# Final_board_R1_1.net
KiCad netlist of a schematic drawn in EAGLE
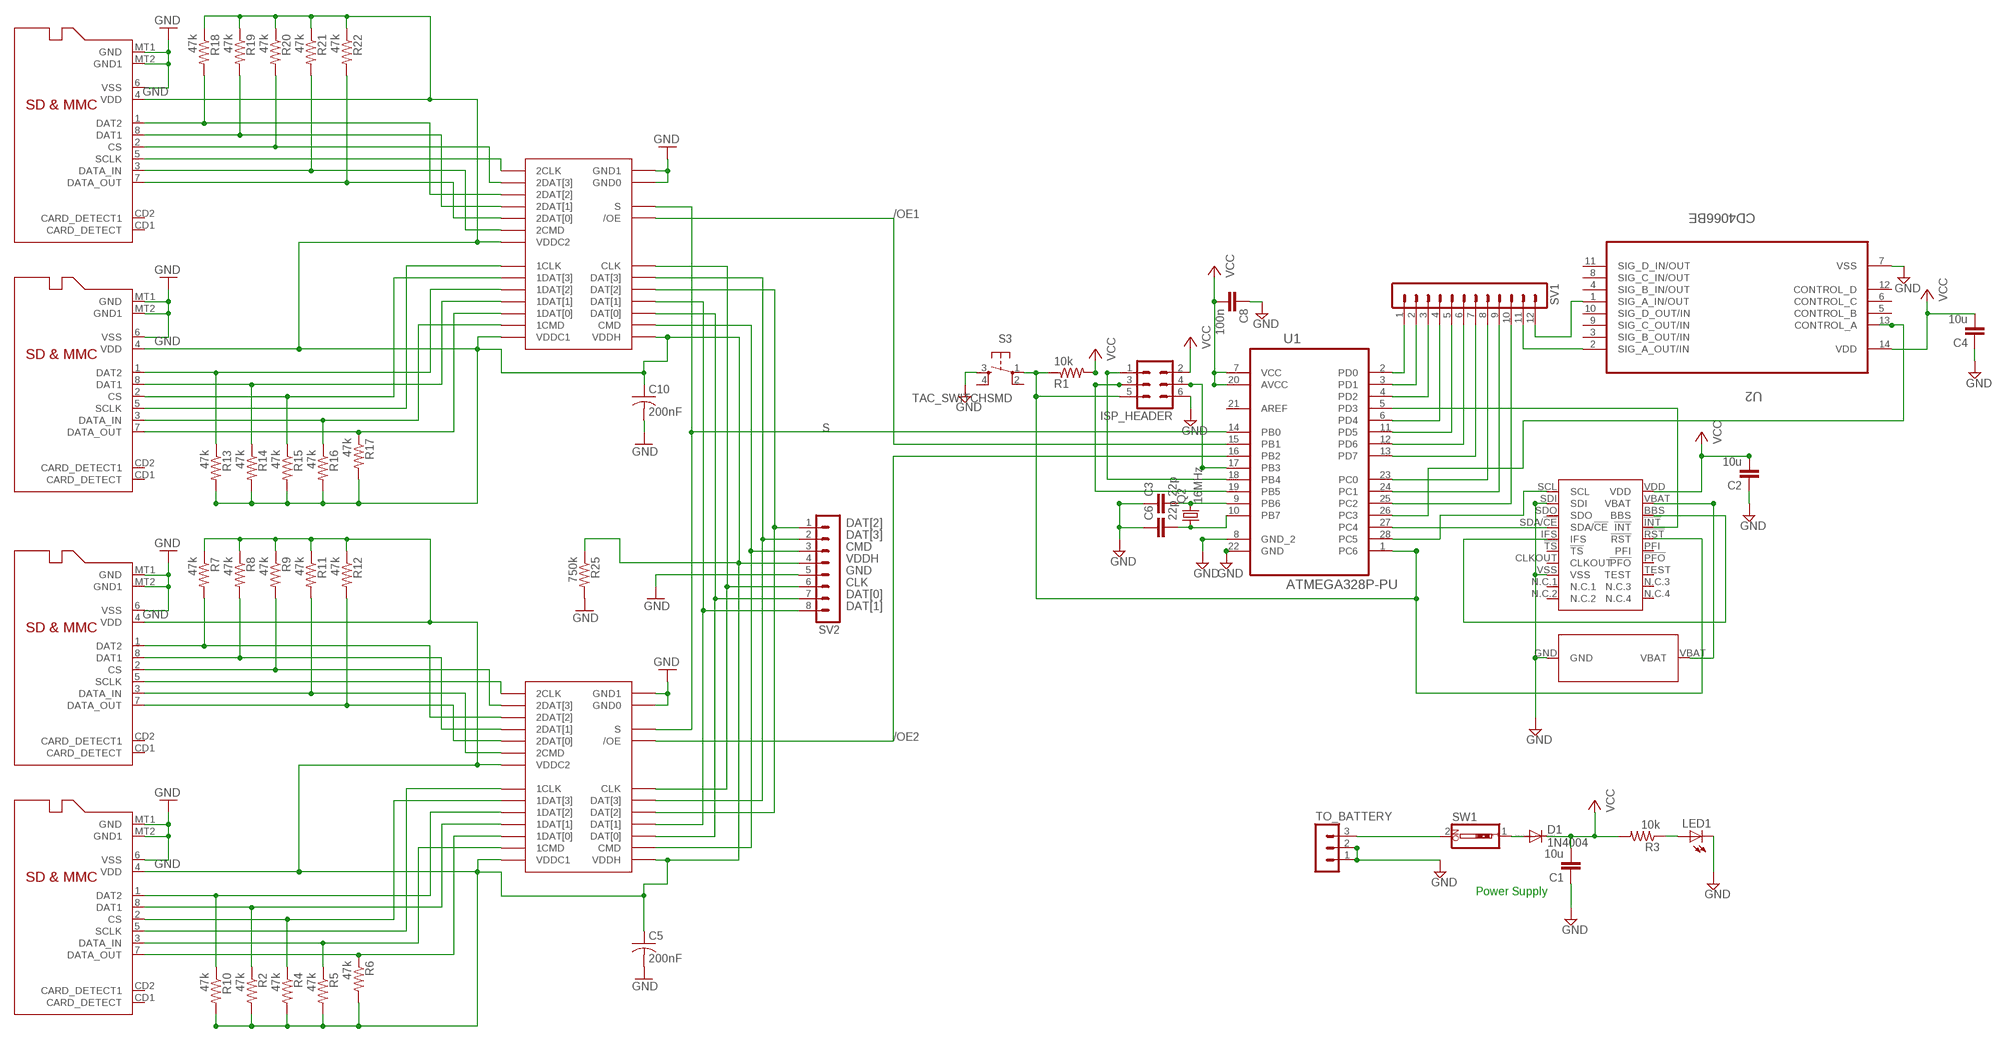
[diagram p0: schematic, sheet 1]

(export (version "E")
  (design (tool "Eeschema 10.0.6"))
  (components
    (comp (ref "+3.6V")
      (value "FSSD06")
      (footprint "eagle-import:MLP-24")
      (libsource (lib "eagle-import") (part "FSSD06"))
    )
    (comp (ref "+3.6V1")
      (value "FSSD06")
      (footprint "eagle-import:MLP-24")
      (libsource (lib "eagle-import") (part "FSSD06"))
    )
    (comp (ref "C1")
      (value "10u")
      (footprint "eagle-import:C0805")
      (libsource (lib "eagle-import") (part "C-EUC0805"))
    )
    (comp (ref "C2")
      (value "10u")
      (footprint "eagle-import:C0805")
      (libsource (lib "eagle-import") (part "C-EUC0805"))
    )
    (comp (ref "C3")
      (value "22p")
      (footprint "eagle-import:C0805")
      (libsource (lib "eagle-import") (part "C-EUC0805"))
    )
    (comp (ref "C4")
      (value "10u")
      (footprint "eagle-import:C0805")
      (libsource (lib "eagle-import") (part "C-EUC0805"))
    )
    (comp (ref "C5")
      (value "200nF")
      (footprint "eagle-import:C0805")
      (libsource (lib "eagle-import") (part "C-USC0805"))
    )
    (comp (ref "C6")
      (value "22p")
      (footprint "eagle-import:C0805")
      (libsource (lib "eagle-import") (part "C-EUC0805"))
    )
    (comp (ref "C8")
      (value "100n")
      (footprint "eagle-import:C0805")
      (libsource (lib "eagle-import") (part "C-EUC0805"))
    )
    (comp (ref "C10")
      (value "200nF")
      (footprint "eagle-import:C0805")
      (libsource (lib "eagle-import") (part "C-USC0805"))
    )
    (comp (ref "D1")
      (value "1N4004")
      (footprint "eagle-import:DO41-10")
      (libsource (lib "eagle-import") (part "1N4004"))
    )
    (comp (ref "ISP_HEADER")
      (value "MA03-2")
      (footprint "eagle-import:MA03-2")
      (libsource (lib "eagle-import") (part "MA03-2"))
    )
    (comp (ref "LED1")
      (value "LEDCHIPLED_0805")
      (footprint "eagle-import:CHIPLED_0805")
      (libsource (lib "eagle-import") (part "LEDCHIPLED_0805"))
    )
    (comp (ref "Q2")
      (value "16MHz")
      (footprint "eagle-import:HC49_S")
      (libsource (lib "eagle-import") (part "CRYSTALHC49S"))
    )
    (comp (ref "R1")
      (value "10k")
      (footprint "eagle-import:R0805")
      (libsource (lib "eagle-import") (part "R-US_R0805"))
    )
    (comp (ref "R2")
      (value "47k")
      (footprint "eagle-import:R0805")
      (libsource (lib "eagle-import") (part "R-US_R0805"))
    )
    (comp (ref "R3")
      (value "10k")
      (footprint "eagle-import:R0805")
      (libsource (lib "eagle-import") (part "R-US_R0805"))
    )
    (comp (ref "R4")
      (value "47k")
      (footprint "eagle-import:R0805")
      (libsource (lib "eagle-import") (part "R-US_R0805"))
    )
    (comp (ref "R5")
      (value "47k")
      (footprint "eagle-import:R0805")
      (libsource (lib "eagle-import") (part "R-US_R0805"))
    )
    (comp (ref "R6")
      (value "47k")
      (footprint "eagle-import:R0805")
      (libsource (lib "eagle-import") (part "R-US_R0805"))
    )
    (comp (ref "R7")
      (value "47k")
      (footprint "eagle-import:R0805")
      (libsource (lib "eagle-import") (part "R-US_R0805"))
    )
    (comp (ref "R8")
      (value "47k")
      (footprint "eagle-import:R0805")
      (libsource (lib "eagle-import") (part "R-US_R0805"))
    )
    (comp (ref "R9")
      (value "47k")
      (footprint "eagle-import:R0805")
      (libsource (lib "eagle-import") (part "R-US_R0805"))
    )
    (comp (ref "R10")
      (value "47k")
      (footprint "eagle-import:R0805")
      (libsource (lib "eagle-import") (part "R-US_R0805"))
    )
    (comp (ref "R11")
      (value "47k")
      (footprint "eagle-import:R0805")
      (libsource (lib "eagle-import") (part "R-US_R0805"))
    )
    (comp (ref "R12")
      (value "47k")
      (footprint "eagle-import:R0805")
      (libsource (lib "eagle-import") (part "R-US_R0805"))
    )
    (comp (ref "R13")
      (value "47k")
      (footprint "eagle-import:R0805")
      (libsource (lib "eagle-import") (part "R-US_R0805"))
    )
    (comp (ref "R14")
      (value "47k")
      (footprint "eagle-import:R0805")
      (libsource (lib "eagle-import") (part "R-US_R0805"))
    )
    (comp (ref "R15")
      (value "47k")
      (footprint "eagle-import:R0805")
      (libsource (lib "eagle-import") (part "R-US_R0805"))
    )
    (comp (ref "R16")
      (value "47k")
      (footprint "eagle-import:R0805")
      (libsource (lib "eagle-import") (part "R-US_R0805"))
    )
    (comp (ref "R17")
      (value "47k")
      (footprint "eagle-import:R0805")
      (libsource (lib "eagle-import") (part "R-US_R0805"))
    )
    (comp (ref "R18")
      (value "47k")
      (footprint "eagle-import:R0805")
      (libsource (lib "eagle-import") (part "R-US_R0805"))
    )
    (comp (ref "R19")
      (value "47k")
      (footprint "eagle-import:R0805")
      (libsource (lib "eagle-import") (part "R-US_R0805"))
    )
    (comp (ref "R20")
      (value "47k")
      (footprint "eagle-import:R0805")
      (libsource (lib "eagle-import") (part "R-US_R0805"))
    )
    (comp (ref "R21")
      (value "47k")
      (footprint "eagle-import:R0805")
      (libsource (lib "eagle-import") (part "R-US_R0805"))
    )
    (comp (ref "R22")
      (value "47k")
      (footprint "eagle-import:R0805")
      (libsource (lib "eagle-import") (part "R-US_R0805"))
    )
    (comp (ref "R25")
      (value "750k")
      (footprint "eagle-import:R0805")
      (libsource (lib "eagle-import") (part "R-US_R0805"))
    )
    (comp (ref "S3")
      (value "TAC_SWITCHSMD")
      (footprint "eagle-import:TACTILE-SWITCH-SMD")
      (libsource (lib "eagle-import") (part "TAC_SWITCHSMD"))
    )
    (comp (ref "SV1")
      (value "MA12-1W")
      (footprint "eagle-import:MA12-1W")
      (libsource (lib "eagle-import") (part "MA12-1W"))
    )
    (comp (ref "SV2")
      (value "MA08-1")
      (footprint "eagle-import:MA08-1")
      (libsource (lib "eagle-import") (part "MA08-1"))
    )
    (comp (ref "SW1")
      (value "SW_DIP-1")
      (footprint "eagle-import:EDG-01")
      (libsource (lib "eagle-import") (part "SW_DIP-1"))
    )
    (comp (ref "TO_BATTERY")
      (value "MA03-1")
      (footprint "eagle-import:MA03-1")
      (libsource (lib "eagle-import") (part "MA03-1"))
    )
    (comp (ref "U$1")
      (value "RTC")
      (footprint "eagle-import:N5")
      (libsource (lib "eagle-import") (part "RTC"))
    )
    (comp (ref "U$2")
      (value "CR2032")
      (footprint "eagle-import:S8421R")
      (libsource (lib "eagle-import") (part "CR2032"))
    )
    (comp (ref "U1")
      (value "ATMEGA328P-PU")
      (footprint "eagle-import:DIP254P762X457-28")
      (libsource (lib "eagle-import") (part "ATMEGA328P-PU"))
    )
    (comp (ref "U2")
      (value "CD4066BE")
      (footprint "eagle-import:DIP254P762X508-14")
      (libsource (lib "eagle-import") (part "CD4066BE"))
    )
    (comp (ref "USD1")
      (value "MICROSD")
      (footprint "eagle-import:MICROSD")
      (libsource (lib "eagle-import") (part "MICROSD"))
    )
    (comp (ref "USD2")
      (value "MICROSD")
      (footprint "eagle-import:MICROSD")
      (libsource (lib "eagle-import") (part "MICROSD"))
    )
    (comp (ref "USD3")
      (value "MICROSD")
      (footprint "eagle-import:MICROSD")
      (libsource (lib "eagle-import") (part "MICROSD"))
    )
    (comp (ref "USD4")
      (value "MICROSD")
      (footprint "eagle-import:MICROSD")
      (libsource (lib "eagle-import") (part "MICROSD"))
    )
  )
  (nets
    (net (code "1") (name "/CLK") (class "Default")
      (node (ref "+3.6V") (pin "CLK") (pinfunction "CLK_CLK") (pintype "bidirectional"))
      (node (ref "+3.6V1") (pin "CLK") (pinfunction "CLK_CLK") (pintype "bidirectional"))
      (node (ref "SV2") (pin "6") (pinfunction "6_6") (pintype "passive"))
    )
    (net (code "2") (name "/CMD") (class "Default")
      (node (ref "+3.6V") (pin "CMD") (pinfunction "CMD_CMD") (pintype "bidirectional"))
      (node (ref "+3.6V1") (pin "CMD") (pinfunction "CMD_CMD") (pintype "bidirectional"))
      (node (ref "SV2") (pin "3") (pinfunction "3_3") (pintype "passive"))
    )
    (net (code "3") (name "/DAT[0]") (class "Default")
      (node (ref "+3.6V") (pin "DAT[0]") (pinfunction "DAT[0]_DAT[0]") (pintype "bidirectional"))
      (node (ref "+3.6V1") (pin "DAT[0]") (pinfunction "DAT[0]_DAT[0]") (pintype "bidirectional"))
      (node (ref "SV2") (pin "7") (pinfunction "7_7") (pintype "passive"))
    )
    (net (code "4") (name "/DAT[1]") (class "Default")
      (node (ref "+3.6V") (pin "DAT[1]") (pinfunction "DAT[1]_DAT[1]") (pintype "bidirectional"))
      (node (ref "+3.6V1") (pin "DAT[1]") (pinfunction "DAT[1]_DAT[1]") (pintype "bidirectional"))
      (node (ref "SV2") (pin "8") (pinfunction "8_8") (pintype "passive"))
    )
    (net (code "5") (name "/DAT[2]") (class "Default")
      (node (ref "+3.6V") (pin "DAT[2]") (pinfunction "DAT[2]_DAT[2]") (pintype "bidirectional"))
      (node (ref "+3.6V1") (pin "DAT[2]") (pinfunction "DAT[2]_DAT[2]") (pintype "bidirectional"))
      (node (ref "SV2") (pin "1") (pinfunction "1_1") (pintype "passive"))
    )
    (net (code "6") (name "/DAT[3]") (class "Default")
      (node (ref "+3.6V") (pin "DAT[3]") (pinfunction "DAT[3]_DAT[3]") (pintype "bidirectional"))
      (node (ref "+3.6V1") (pin "DAT[3]") (pinfunction "DAT[3]_DAT[3]") (pintype "bidirectional"))
      (node (ref "SV2") (pin "2") (pinfunction "2_2") (pintype "passive"))
    )
    (net (code "7") (name "/S") (class "Default")
      (node (ref "+3.6V") (pin "S") (pinfunction "S_S") (pintype "bidirectional"))
      (node (ref "+3.6V1") (pin "S") (pinfunction "S_S") (pintype "bidirectional"))
      (node (ref "U1") (pin "14") (pinfunction "PB0_14") (pintype "bidirectional"))
    )
    (net (code "8") (name "/VDDH") (class "Default")
      (node (ref "+3.6V") (pin "VDDC1") (pinfunction "VDDC1_VDDC1") (pintype "bidirectional"))
      (node (ref "+3.6V") (pin "VDDC2") (pinfunction "VDDC2_VDDC2") (pintype "bidirectional"))
      (node (ref "+3.6V") (pin "VDDH") (pinfunction "VDDH_VDDH") (pintype "bidirectional"))
      (node (ref "+3.6V1") (pin "VDDC1") (pinfunction "VDDC1_VDDC1") (pintype "bidirectional"))
      (node (ref "+3.6V1") (pin "VDDC2") (pinfunction "VDDC2_VDDC2") (pintype "bidirectional"))
      (node (ref "+3.6V1") (pin "VDDH") (pinfunction "VDDH_VDDH") (pintype "bidirectional"))
      (node (ref "C10") (pin "1") (pinfunction "1_1") (pintype "passive"))
      (node (ref "C5") (pin "1") (pinfunction "1_1") (pintype "passive"))
      (node (ref "R10") (pin "2") (pinfunction "2_2") (pintype "passive"))
      (node (ref "R11") (pin "1") (pinfunction "1_1") (pintype "passive"))
      (node (ref "R12") (pin "1") (pinfunction "1_1") (pintype "passive"))
      (node (ref "R13") (pin "2") (pinfunction "2_2") (pintype "passive"))
      (node (ref "R14") (pin "2") (pinfunction "2_2") (pintype "passive"))
      (node (ref "R15") (pin "2") (pinfunction "2_2") (pintype "passive"))
      (node (ref "R16") (pin "2") (pinfunction "2_2") (pintype "passive"))
      (node (ref "R17") (pin "2") (pinfunction "2_2") (pintype "passive"))
      (node (ref "R18") (pin "1") (pinfunction "1_1") (pintype "passive"))
      (node (ref "R19") (pin "1") (pinfunction "1_1") (pintype "passive"))
      (node (ref "R2") (pin "2") (pinfunction "2_2") (pintype "passive"))
      (node (ref "R20") (pin "1") (pinfunction "1_1") (pintype "passive"))
      (node (ref "R21") (pin "1") (pinfunction "1_1") (pintype "passive"))
      (node (ref "R22") (pin "1") (pinfunction "1_1") (pintype "passive"))
      (node (ref "R25") (pin "1") (pinfunction "1_1") (pintype "passive"))
      (node (ref "R4") (pin "2") (pinfunction "2_2") (pintype "passive"))
      (node (ref "R5") (pin "2") (pinfunction "2_2") (pintype "passive"))
      (node (ref "R6") (pin "2") (pinfunction "2_2") (pintype "passive"))
      (node (ref "R7") (pin "1") (pinfunction "1_1") (pintype "passive"))
      (node (ref "R8") (pin "1") (pinfunction "1_1") (pintype "passive"))
      (node (ref "R9") (pin "1") (pinfunction "1_1") (pintype "passive"))
      (node (ref "SV2") (pin "4") (pinfunction "4_4") (pintype "passive"))
      (node (ref "USD1") (pin "4") (pinfunction "VDD_4") (pintype "power_in"))
      (node (ref "USD2") (pin "4") (pinfunction "VDD_4") (pintype "power_in"))
      (node (ref "USD3") (pin "4") (pinfunction "VDD_4") (pintype "power_in"))
      (node (ref "USD4") (pin "4") (pinfunction "VDD_4") (pintype "power_in"))
    )
    (net (code "9") (name "/{slash}OE1") (class "Default")
      (node (ref "+3.6V1") (pin "/OE") (pinfunction "/OE_/OE") (pintype "bidirectional"))
      (node (ref "U1") (pin "15") (pinfunction "PB1_15") (pintype "bidirectional"))
    )
    (net (code "10") (name "/{slash}OE2") (class "Default")
      (node (ref "+3.6V") (pin "/OE") (pinfunction "/OE_/OE") (pintype "bidirectional"))
      (node (ref "U1") (pin "16") (pinfunction "PB2_16") (pintype "bidirectional"))
    )
    (net (code "11") (name "GND") (class "Default")
      (node (ref "+3.6V") (pin "GND0") (pinfunction "GND0_GND0") (pintype "bidirectional"))
      (node (ref "+3.6V") (pin "GND1") (pinfunction "GND1_GND1") (pintype "bidirectional"))
      (node (ref "+3.6V1") (pin "GND0") (pinfunction "GND0_GND0") (pintype "bidirectional"))
      (node (ref "+3.6V1") (pin "GND1") (pinfunction "GND1_GND1") (pintype "bidirectional"))
      (node (ref "C1") (pin "1") (pinfunction "1_1") (pintype "passive"))
      (node (ref "C10") (pin "2") (pinfunction "2_2") (pintype "passive"))
      (node (ref "C2") (pin "1") (pinfunction "1_1") (pintype "passive"))
      (node (ref "C3") (pin "1") (pinfunction "1_1") (pintype "passive"))
      (node (ref "C4") (pin "1") (pinfunction "1_1") (pintype "passive"))
      (node (ref "C5") (pin "2") (pinfunction "2_2") (pintype "passive"))
      (node (ref "C6") (pin "1") (pinfunction "1_1") (pintype "passive"))
      (node (ref "C8") (pin "1") (pinfunction "1_1") (pintype "passive"))
      (node (ref "ISP_HEADER") (pin "6") (pinfunction "6_6") (pintype "passive"))
      (node (ref "LED1") (pin "C") (pinfunction "C_C") (pintype "passive"))
      (node (ref "R25") (pin "2") (pinfunction "2_2") (pintype "passive"))
      (node (ref "S3") (pin "3") (pinfunction "3_3") (pintype "passive"))
      (node (ref "SV2") (pin "5") (pinfunction "5_5") (pintype "passive"))
      (node (ref "TO_BATTERY") (pin "1") (pinfunction "1_1") (pintype "passive"))
      (node (ref "TO_BATTERY") (pin "2") (pinfunction "2_2") (pintype "passive"))
      (node (ref "U$1") (pin "SDI") (pinfunction "SDI_SDI") (pintype "bidirectional"))
      (node (ref "U$1") (pin "VSS") (pinfunction "VSS_VSS") (pintype "bidirectional"))
      (node (ref "U$2") (pin "GND") (pinfunction "GND_GND") (pintype "bidirectional"))
      (node (ref "U1") (pin "22") (pinfunction "GND_22") (pintype "passive"))
      (node (ref "U1") (pin "8") (pinfunction "GND_2_8") (pintype "passive"))
      (node (ref "U2") (pin "7") (pinfunction "VSS_7") (pintype "passive"))
      (node (ref "USD1") (pin "6") (pinfunction "VSS_6") (pintype "power_in"))
      (node (ref "USD1") (pin "MT1") (pinfunction "GND_MT1") (pintype "power_in"))
      (node (ref "USD1") (pin "MT2") (pinfunction "GND1_MT2") (pintype "power_in"))
      (node (ref "USD2") (pin "6") (pinfunction "VSS_6") (pintype "power_in"))
      (node (ref "USD2") (pin "MT1") (pinfunction "GND_MT1") (pintype "power_in"))
      (node (ref "USD2") (pin "MT2") (pinfunction "GND1_MT2") (pintype "power_in"))
      (node (ref "USD3") (pin "6") (pinfunction "VSS_6") (pintype "power_in"))
      (node (ref "USD3") (pin "MT1") (pinfunction "GND_MT1") (pintype "power_in"))
      (node (ref "USD3") (pin "MT2") (pinfunction "GND1_MT2") (pintype "power_in"))
      (node (ref "USD4") (pin "6") (pinfunction "VSS_6") (pintype "power_in"))
      (node (ref "USD4") (pin "MT1") (pinfunction "GND_MT1") (pintype "power_in"))
      (node (ref "USD4") (pin "MT2") (pinfunction "GND1_MT2") (pintype "power_in"))
    )
    (net (code "12") (name "Net-(+3.6V-2CLK)") (class "Default")
      (node (ref "+3.6V") (pin "2CLCK") (pinfunction "2CLK_2CLCK") (pintype "bidirectional"))
      (node (ref "USD2") (pin "5") (pinfunction "SCLK_5") (pintype "input"))
    )
    (net (code "13") (name "Net-(+3.6V1-2CLK)") (class "Default")
      (node (ref "+3.6V1") (pin "2CLCK") (pinfunction "2CLK_2CLCK") (pintype "bidirectional"))
      (node (ref "USD4") (pin "5") (pinfunction "SCLK_5") (pintype "input"))
    )
    (net (code "14") (name "Net-(D1-PadA)") (class "Default")
      (node (ref "D1") (pin "A") (pinfunction "A_A") (pintype "passive"))
      (node (ref "SW1") (pin "1") (pinfunction "1_1") (pintype "passive"))
    )
    (net (code "15") (name "Net-(LED1-PadA)") (class "Default")
      (node (ref "LED1") (pin "A") (pinfunction "A_A") (pintype "passive"))
      (node (ref "R3") (pin "1") (pinfunction "1_1") (pintype "passive"))
    )
    (net (code "16") (name "Net-(SW1-Pad2)") (class "Default")
      (node (ref "SW1") (pin "2") (pinfunction "2_2") (pintype "passive"))
      (node (ref "TO_BATTERY") (pin "3") (pinfunction "3_3") (pintype "passive"))
    )
    (net (code "17") (name "Net-(U$1-PadBBS)") (class "Default")
      (node (ref "U$1") (pin "BBS") (pinfunction "BBS_BBS") (pintype "bidirectional"))
      (node (ref "U$1") (pin "IFS") (pinfunction "IFS_IFS") (pintype "bidirectional"))
    )
    (net (code "18") (name "Net-(U$1-PadVBAT)") (class "Default")
      (node (ref "U$1") (pin "VBAT") (pinfunction "VBAT_VBAT") (pintype "bidirectional"))
      (node (ref "U$2") (pin "VBAT") (pinfunction "VBAT_VBAT") (pintype "bidirectional"))
    )
    (net (code "19") (name "Net-(U$1-SDA{slash}~{CE})") (class "Default")
      (node (ref "U$1") (pin "SDA/!CE") (pinfunction "SDA/~{CE}_SDA/!CE") (pintype "bidirectional"))
      (node (ref "U1") (pin "27") (pinfunction "PC4_27") (pintype "bidirectional"))
    )
    (net (code "20") (name "Net-(U$1-~{INT})") (class "Default")
      (node (ref "U$1") (pin "!INT") (pinfunction "~{INT}_!INT") (pintype "bidirectional"))
      (node (ref "U1") (pin "5") (pinfunction "PD3_5") (pintype "bidirectional"))
    )
    (net (code "21") (name "Net-(U$1-~{RST})") (class "Default")
      (node (ref "ISP_HEADER") (pin "5") (pinfunction "5_5") (pintype "passive"))
      (node (ref "R1") (pin "1") (pinfunction "1_1") (pintype "passive"))
      (node (ref "S3") (pin "1") (pinfunction "1_1") (pintype "passive"))
      (node (ref "U$1") (pin "!RST") (pinfunction "~{RST}_!RST") (pintype "bidirectional"))
      (node (ref "U1") (pin "1") (pinfunction "PC6_1") (pintype "bidirectional"))
    )
    (net (code "22") (name "Net-(U1-PB3)") (class "Default")
      (node (ref "ISP_HEADER") (pin "4") (pinfunction "4_4") (pintype "passive"))
      (node (ref "U1") (pin "17") (pinfunction "PB3_17") (pintype "bidirectional"))
    )
    (net (code "23") (name "Net-(U1-PB4)") (class "Default")
      (node (ref "ISP_HEADER") (pin "1") (pinfunction "1_1") (pintype "passive"))
      (node (ref "U1") (pin "18") (pinfunction "PB4_18") (pintype "bidirectional"))
    )
    (net (code "24") (name "Net-(U1-PB5)") (class "Default")
      (node (ref "ISP_HEADER") (pin "3") (pinfunction "3_3") (pintype "passive"))
      (node (ref "U1") (pin "19") (pinfunction "PB5_19") (pintype "bidirectional"))
    )
    (net (code "25") (name "Net-(U1-PB6)") (class "Default")
      (node (ref "C3") (pin "2") (pinfunction "2_2") (pintype "passive"))
      (node (ref "Q2") (pin "2") (pinfunction "2_2") (pintype "passive"))
      (node (ref "U1") (pin "9") (pinfunction "PB6_9") (pintype "bidirectional"))
    )
    (net (code "26") (name "Net-(U1-PB7)") (class "Default")
      (node (ref "C6") (pin "2") (pinfunction "2_2") (pintype "passive"))
      (node (ref "Q2") (pin "1") (pinfunction "1_1") (pintype "passive"))
      (node (ref "U1") (pin "10") (pinfunction "PB7_10") (pintype "bidirectional"))
    )
    (net (code "27") (name "Net-(U1-PC0)") (class "Default")
      (node (ref "SV1") (pin "8") (pinfunction "8_8") (pintype "passive"))
      (node (ref "U1") (pin "23") (pinfunction "PC0_23") (pintype "bidirectional"))
    )
    (net (code "28") (name "Net-(U1-PC1)") (class "Default")
      (node (ref "SV1") (pin "9") (pinfunction "9_9") (pintype "passive"))
      (node (ref "U1") (pin "24") (pinfunction "PC1_24") (pintype "bidirectional"))
    )
    (net (code "29") (name "Net-(U1-PC2)") (class "Default")
      (node (ref "SV1") (pin "10") (pinfunction "10_10") (pintype "passive"))
      (node (ref "U1") (pin "25") (pinfunction "PC2_25") (pintype "bidirectional"))
    )
    (net (code "30") (name "Net-(U1-PC3)") (class "Default")
      (node (ref "U1") (pin "26") (pinfunction "PC3_26") (pintype "bidirectional"))
      (node (ref "U2") (pin "13") (pinfunction "CONTROL_A_13") (pintype "input"))
    )
    (net (code "31") (name "Net-(U1-PC5)") (class "Default")
      (node (ref "U$1") (pin "SCL") (pinfunction "SCL_SCL") (pintype "bidirectional"))
      (node (ref "U1") (pin "28") (pinfunction "PC5_28") (pintype "bidirectional"))
    )
    (net (code "32") (name "Net-(U1-PD0)") (class "Default")
      (node (ref "SV1") (pin "1") (pinfunction "1_1") (pintype "passive"))
      (node (ref "U1") (pin "2") (pinfunction "PD0_2") (pintype "bidirectional"))
    )
    (net (code "33") (name "Net-(U1-PD1)") (class "Default")
      (node (ref "SV1") (pin "2") (pinfunction "2_2") (pintype "passive"))
      (node (ref "U1") (pin "3") (pinfunction "PD1_3") (pintype "bidirectional"))
    )
    (net (code "34") (name "Net-(U1-PD2)") (class "Default")
      (node (ref "SV1") (pin "3") (pinfunction "3_3") (pintype "passive"))
      (node (ref "U1") (pin "4") (pinfunction "PD2_4") (pintype "bidirectional"))
    )
    (net (code "35") (name "Net-(U1-PD4)") (class "Default")
      (node (ref "SV1") (pin "4") (pinfunction "4_4") (pintype "passive"))
      (node (ref "U1") (pin "6") (pinfunction "PD4_6") (pintype "bidirectional"))
    )
    (net (code "36") (name "Net-(U1-PD5)") (class "Default")
      (node (ref "SV1") (pin "5") (pinfunction "5_5") (pintype "passive"))
      (node (ref "U1") (pin "11") (pinfunction "PD5_11") (pintype "bidirectional"))
    )
    (net (code "37") (name "Net-(U1-PD6)") (class "Default")
      (node (ref "SV1") (pin "6") (pinfunction "6_6") (pintype "passive"))
      (node (ref "U1") (pin "12") (pinfunction "PD6_12") (pintype "bidirectional"))
    )
    (net (code "38") (name "Net-(U1-PD7)") (class "Default")
      (node (ref "SV1") (pin "7") (pinfunction "7_7") (pintype "passive"))
      (node (ref "U1") (pin "13") (pinfunction "PD7_13") (pintype "bidirectional"))
    )
    (net (code "39") (name "Net-(U2-SIG_A_IN{slash}OUT)") (class "Default")
      (node (ref "SV1") (pin "12") (pinfunction "12_12") (pintype "passive"))
      (node (ref "U2") (pin "1") (pinfunction "SIG_A_IN/OUT_1") (pintype "bidirectional"))
    )
    (net (code "40") (name "Net-(U2-SIG_A_OUT{slash}IN)") (class "Default")
      (node (ref "SV1") (pin "11") (pinfunction "11_11") (pintype "passive"))
      (node (ref "U2") (pin "2") (pinfunction "SIG_A_OUT/IN_2") (pintype "bidirectional"))
    )
    (net (code "41") (name "Net-(USD1-CS)") (class "Default")
      (node (ref "+3.6V") (pin "1DAT[3]") (pinfunction "1DAT[3]_1DAT[3]") (pintype "bidirectional"))
      (node (ref "R4") (pin "1") (pinfunction "1_1") (pintype "passive"))
      (node (ref "USD1") (pin "2") (pinfunction "CS_2") (pintype "input"))
    )
    (net (code "42") (name "Net-(USD1-DAT1)") (class "Default")
      (node (ref "+3.6V") (pin "1DAT[1]") (pinfunction "1DAT[1]_1DAT[1]") (pintype "bidirectional"))
      (node (ref "R2") (pin "1") (pinfunction "1_1") (pintype "passive"))
      (node (ref "USD1") (pin "8") (pinfunction "DAT1_8") (pintype "bidirectional"))
    )
    (net (code "43") (name "Net-(USD1-DAT2)") (class "Default")
      (node (ref "+3.6V") (pin "1DAT[2]") (pinfunction "1DAT[2]_1DAT[2]") (pintype "bidirectional"))
      (node (ref "R10") (pin "1") (pinfunction "1_1") (pintype "passive"))
      (node (ref "USD1") (pin "1") (pinfunction "DAT2_1") (pintype "bidirectional"))
    )
    (net (code "44") (name "Net-(USD1-DATA_IN)") (class "Default")
      (node (ref "+3.6V") (pin "1CMD") (pinfunction "1CMD_1CMD") (pintype "bidirectional"))
      (node (ref "R5") (pin "1") (pinfunction "1_1") (pintype "passive"))
      (node (ref "USD1") (pin "3") (pinfunction "DATA_IN_3") (pintype "input"))
    )
    (net (code "45") (name "Net-(USD1-DATA_OUT)") (class "Default")
      (node (ref "+3.6V") (pin "1DAT[0]") (pinfunction "1DAT[0]_1DAT[0]") (pintype "bidirectional"))
      (node (ref "R6") (pin "1") (pinfunction "1_1") (pintype "passive"))
      (node (ref "USD1") (pin "7") (pinfunction "DATA_OUT_7") (pintype "output"))
    )
    (net (code "46") (name "Net-(USD1-SCLK)") (class "Default")
      (node (ref "+3.6V") (pin "1CLK") (pinfunction "1CLK_1CLK") (pintype "bidirectional"))
      (node (ref "USD1") (pin "5") (pinfunction "SCLK_5") (pintype "input"))
    )
    (net (code "47") (name "Net-(USD2-CS)") (class "Default")
      (node (ref "+3.6V") (pin "2DAT[3]") (pinfunction "2DAT[3]_2DAT[3]") (pintype "bidirectional"))
      (node (ref "R9") (pin "2") (pinfunction "2_2") (pintype "passive"))
      (node (ref "USD2") (pin "2") (pinfunction "CS_2") (pintype "input"))
    )
    (net (code "48") (name "Net-(USD2-DAT1)") (class "Default")
      (node (ref "+3.6V") (pin "2DAT[1]") (pinfunction "2DAT[1]_2DAT[1]") (pintype "bidirectional"))
      (node (ref "R8") (pin "2") (pinfunction "2_2") (pintype "passive"))
      (node (ref "USD2") (pin "8") (pinfunction "DAT1_8") (pintype "bidirectional"))
    )
    (net (code "49") (name "Net-(USD2-DAT2)") (class "Default")
      (node (ref "+3.6V") (pin "2DAT[2]") (pinfunction "2DAT[2]_2DAT[2]") (pintype "bidirectional"))
      (node (ref "R7") (pin "2") (pinfunction "2_2") (pintype "passive"))
      (node (ref "USD2") (pin "1") (pinfunction "DAT2_1") (pintype "bidirectional"))
    )
    (net (code "50") (name "Net-(USD2-DATA_IN)") (class "Default")
      (node (ref "+3.6V") (pin "2CMD") (pinfunction "2CMD_2CMD") (pintype "bidirectional"))
      (node (ref "R11") (pin "2") (pinfunction "2_2") (pintype "passive"))
      (node (ref "USD2") (pin "3") (pinfunction "DATA_IN_3") (pintype "input"))
    )
    (net (code "51") (name "Net-(USD2-DATA_OUT)") (class "Default")
      (node (ref "+3.6V") (pin "2DAT[0]") (pinfunction "2DAT[0]_2DAT[0]") (pintype "bidirectional"))
      (node (ref "R12") (pin "2") (pinfunction "2_2") (pintype "passive"))
      (node (ref "USD2") (pin "7") (pinfunction "DATA_OUT_7") (pintype "output"))
    )
    (net (code "52") (name "Net-(USD3-CS)") (class "Default")
      (node (ref "+3.6V1") (pin "1DAT[3]") (pinfunction "1DAT[3]_1DAT[3]") (pintype "bidirectional"))
      (node (ref "R15") (pin "1") (pinfunction "1_1") (pintype "passive"))
      (node (ref "USD3") (pin "2") (pinfunction "CS_2") (pintype "input"))
    )
    (net (code "53") (name "Net-(USD3-DAT1)") (class "Default")
      (node (ref "+3.6V1") (pin "1DAT[1]") (pinfunction "1DAT[1]_1DAT[1]") (pintype "bidirectional"))
      (node (ref "R14") (pin "1") (pinfunction "1_1") (pintype "passive"))
      (node (ref "USD3") (pin "8") (pinfunction "DAT1_8") (pintype "bidirectional"))
    )
    (net (code "54") (name "Net-(USD3-DAT2)") (class "Default")
      (node (ref "+3.6V1") (pin "1DAT[2]") (pinfunction "1DAT[2]_1DAT[2]") (pintype "bidirectional"))
      (node (ref "R13") (pin "1") (pinfunction "1_1") (pintype "passive"))
      (node (ref "USD3") (pin "1") (pinfunction "DAT2_1") (pintype "bidirectional"))
    )
    (net (code "55") (name "Net-(USD3-DATA_IN)") (class "Default")
      (node (ref "+3.6V1") (pin "1CMD") (pinfunction "1CMD_1CMD") (pintype "bidirectional"))
      (node (ref "R16") (pin "1") (pinfunction "1_1") (pintype "passive"))
      (node (ref "USD3") (pin "3") (pinfunction "DATA_IN_3") (pintype "input"))
    )
    (net (code "56") (name "Net-(USD3-DATA_OUT)") (class "Default")
      (node (ref "+3.6V1") (pin "1DAT[0]") (pinfunction "1DAT[0]_1DAT[0]") (pintype "bidirectional"))
      (node (ref "R17") (pin "1") (pinfunction "1_1") (pintype "passive"))
      (node (ref "USD3") (pin "7") (pinfunction "DATA_OUT_7") (pintype "output"))
    )
    (net (code "57") (name "Net-(USD3-SCLK)") (class "Default")
      (node (ref "+3.6V1") (pin "1CLK") (pinfunction "1CLK_1CLK") (pintype "bidirectional"))
      (node (ref "USD3") (pin "5") (pinfunction "SCLK_5") (pintype "input"))
    )
    (net (code "58") (name "Net-(USD4-CS)") (class "Default")
      (node (ref "+3.6V1") (pin "2DAT[3]") (pinfunction "2DAT[3]_2DAT[3]") (pintype "bidirectional"))
      (node (ref "R20") (pin "2") (pinfunction "2_2") (pintype "passive"))
      (node (ref "USD4") (pin "2") (pinfunction "CS_2") (pintype "input"))
    )
    (net (code "59") (name "Net-(USD4-DAT1)") (class "Default")
      (node (ref "+3.6V1") (pin "2DAT[1]") (pinfunction "2DAT[1]_2DAT[1]") (pintype "bidirectional"))
      (node (ref "R19") (pin "2") (pinfunction "2_2") (pintype "passive"))
      (node (ref "USD4") (pin "8") (pinfunction "DAT1_8") (pintype "bidirectional"))
    )
    (net (code "60") (name "Net-(USD4-DAT2)") (class "Default")
      (node (ref "+3.6V1") (pin "2DAT[2]") (pinfunction "2DAT[2]_2DAT[2]") (pintype "bidirectional"))
      (node (ref "R18") (pin "2") (pinfunction "2_2") (pintype "passive"))
      (node (ref "USD4") (pin "1") (pinfunction "DAT2_1") (pintype "bidirectional"))
    )
    (net (code "61") (name "Net-(USD4-DATA_IN)") (class "Default")
      (node (ref "+3.6V1") (pin "2CMD") (pinfunction "2CMD_2CMD") (pintype "bidirectional"))
      (node (ref "R21") (pin "2") (pinfunction "2_2") (pintype "passive"))
      (node (ref "USD4") (pin "3") (pinfunction "DATA_IN_3") (pintype "input"))
    )
    (net (code "62") (name "Net-(USD4-DATA_OUT)") (class "Default")
      (node (ref "+3.6V1") (pin "2DAT[0]") (pinfunction "2DAT[0]_2DAT[0]") (pintype "bidirectional"))
      (node (ref "R22") (pin "2") (pinfunction "2_2") (pintype "passive"))
      (node (ref "USD4") (pin "7") (pinfunction "DATA_OUT_7") (pintype "output"))
    )
    (net (code "63") (name "VCC") (class "Default")
      (node (ref "C1") (pin "2") (pinfunction "2_2") (pintype "passive"))
      (node (ref "C2") (pin "2") (pinfunction "2_2") (pintype "passive"))
      (node (ref "C4") (pin "2") (pinfunction "2_2") (pintype "passive"))
      (node (ref "C8") (pin "2") (pinfunction "2_2") (pintype "passive"))
      (node (ref "D1") (pin "C") (pinfunction "C_C") (pintype "passive"))
      (node (ref "ISP_HEADER") (pin "2") (pinfunction "2_2") (pintype "passive"))
      (node (ref "R1") (pin "2") (pinfunction "2_2") (pintype "passive"))
      (node (ref "R3") (pin "2") (pinfunction "2_2") (pintype "passive"))
      (node (ref "U$1") (pin "VDD") (pinfunction "VDD_VDD") (pintype "bidirectional"))
      (node (ref "U1") (pin "20") (pinfunction "AVCC_20") (pintype "power_in"))
      (node (ref "U1") (pin "7") (pinfunction "VCC_7") (pintype "power_in"))
      (node (ref "U2") (pin "14") (pinfunction "VDD_14") (pintype "power_in"))
    )
    (net (code "64") (name "unconnected-(S3-Pad2)") (class "Default")
      (node (ref "S3") (pin "2") (pinfunction "2_2") (pintype "passive"))
    )
    (net (code "65") (name "unconnected-(S3-Pad4)") (class "Default")
      (node (ref "S3") (pin "4") (pinfunction "4_4") (pintype "passive"))
    )
    (net (code "66") (name "unconnected-(U$1-PadCLKOUT)") (class "Default")
      (node (ref "U$1") (pin "CLKOUT") (pinfunction "CLKOUT_CLKOUT") (pintype "bidirectional"))
    )
    (net (code "67") (name "unconnected-(U$1-PadN.C.1)") (class "Default")
      (node (ref "U$1") (pin "N.C.1") (pinfunction "N.C.1_N.C.1") (pintype "bidirectional"))
    )
    (net (code "68") (name "unconnected-(U$1-PadN.C.2)") (class "Default")
      (node (ref "U$1") (pin "N.C.2") (pinfunction "N.C.2_N.C.2") (pintype "bidirectional"))
    )
    (net (code "69") (name "unconnected-(U$1-PadN.C.3)") (class "Default")
      (node (ref "U$1") (pin "N.C.3") (pinfunction "N.C.3_N.C.3") (pintype "bidirectional"))
    )
    (net (code "70") (name "unconnected-(U$1-PadN.C.4)") (class "Default")
      (node (ref "U$1") (pin "N.C.4") (pinfunction "N.C.4_N.C.4") (pintype "bidirectional"))
    )
    (net (code "71") (name "unconnected-(U$1-PadPFI)") (class "Default")
      (node (ref "U$1") (pin "PFI") (pinfunction "PFI_PFI") (pintype "bidirectional"))
    )
    (net (code "72") (name "unconnected-(U$1-PadSDO)") (class "Default")
      (node (ref "U$1") (pin "SDO") (pinfunction "SDO_SDO") (pintype "bidirectional"))
    )
    (net (code "73") (name "unconnected-(U$1-PadTEST)") (class "Default")
      (node (ref "U$1") (pin "TEST") (pinfunction "TEST_TEST") (pintype "bidirectional"))
    )
    (net (code "74") (name "unconnected-(U$1-~{PFO}-Pad!PFO)") (class "Default")
      (node (ref "U$1") (pin "!PFO") (pinfunction "~{PFO}_!PFO") (pintype "bidirectional"))
    )
    (net (code "75") (name "unconnected-(U$1-~{TS}-Pad!TS)") (class "Default")
      (node (ref "U$1") (pin "!TS") (pinfunction "~{TS}_!TS") (pintype "bidirectional"))
    )
    (net (code "76") (name "unconnected-(U1-AREF-Pad21)") (class "Default")
      (node (ref "U1") (pin "21") (pinfunction "AREF_21") (pintype "input"))
    )
    (net (code "77") (name "unconnected-(U2-CONTROL_B-Pad5)") (class "Default")
      (node (ref "U2") (pin "5") (pinfunction "CONTROL_B_5") (pintype "input"))
    )
    (net (code "78") (name "unconnected-(U2-CONTROL_C-Pad6)") (class "Default")
      (node (ref "U2") (pin "6") (pinfunction "CONTROL_C_6") (pintype "input"))
    )
    (net (code "79") (name "unconnected-(U2-CONTROL_D-Pad12)") (class "Default")
      (node (ref "U2") (pin "12") (pinfunction "CONTROL_D_12") (pintype "input"))
    )
    (net (code "80") (name "unconnected-(U2-SIG_B_IN{slash}OUT-Pad4)") (class "Default")
      (node (ref "U2") (pin "4") (pinfunction "SIG_B_IN/OUT_4") (pintype "bidirectional"))
    )
    (net (code "81") (name "unconnected-(U2-SIG_B_OUT{slash}IN-Pad3)") (class "Default")
      (node (ref "U2") (pin "3") (pinfunction "SIG_B_OUT/IN_3") (pintype "bidirectional"))
    )
    (net (code "82") (name "unconnected-(U2-SIG_C_IN{slash}OUT-Pad8)") (class "Default")
      (node (ref "U2") (pin "8") (pinfunction "SIG_C_IN/OUT_8") (pintype "bidirectional"))
    )
    (net (code "83") (name "unconnected-(U2-SIG_C_OUT{slash}IN-Pad9)") (class "Default")
      (node (ref "U2") (pin "9") (pinfunction "SIG_C_OUT/IN_9") (pintype "bidirectional"))
    )
    (net (code "84") (name "unconnected-(U2-SIG_D_IN{slash}OUT-Pad11)") (class "Default")
      (node (ref "U2") (pin "11") (pinfunction "SIG_D_IN/OUT_11") (pintype "bidirectional"))
    )
    (net (code "85") (name "unconnected-(U2-SIG_D_OUT{slash}IN-Pad10)") (class "Default")
      (node (ref "U2") (pin "10") (pinfunction "SIG_D_OUT/IN_10") (pintype "bidirectional"))
    )
    (net (code "86") (name "unconnected-(USD1-CARD_DETECT-PadCD1)") (class "Default")
      (node (ref "USD1") (pin "CD1") (pinfunction "CARD_DETECT_CD1") (pintype "passive"))
    )
    (net (code "87") (name "unconnected-(USD1-CARD_DETECT1-PadCD2)") (class "Default")
      (node (ref "USD1") (pin "CD2") (pinfunction "CARD_DETECT1_CD2") (pintype "passive"))
    )
    (net (code "88") (name "unconnected-(USD2-CARD_DETECT-PadCD1)") (class "Default")
      (node (ref "USD2") (pin "CD1") (pinfunction "CARD_DETECT_CD1") (pintype "passive"))
    )
    (net (code "89") (name "unconnected-(USD2-CARD_DETECT1-PadCD2)") (class "Default")
      (node (ref "USD2") (pin "CD2") (pinfunction "CARD_DETECT1_CD2") (pintype "passive"))
    )
    (net (code "90") (name "unconnected-(USD3-CARD_DETECT-PadCD1)") (class "Default")
      (node (ref "USD3") (pin "CD1") (pinfunction "CARD_DETECT_CD1") (pintype "passive"))
    )
    (net (code "91") (name "unconnected-(USD3-CARD_DETECT1-PadCD2)") (class "Default")
      (node (ref "USD3") (pin "CD2") (pinfunction "CARD_DETECT1_CD2") (pintype "passive"))
    )
    (net (code "92") (name "unconnected-(USD4-CARD_DETECT-PadCD1)") (class "Default")
      (node (ref "USD4") (pin "CD1") (pinfunction "CARD_DETECT_CD1") (pintype "passive"))
    )
    (net (code "93") (name "unconnected-(USD4-CARD_DETECT1-PadCD2)") (class "Default")
      (node (ref "USD4") (pin "CD2") (pinfunction "CARD_DETECT1_CD2") (pintype "passive"))
    )
  )
)
